# OD12_LCD__Layout.net
KiCad netlist of a schematic drawn in Altium Designer
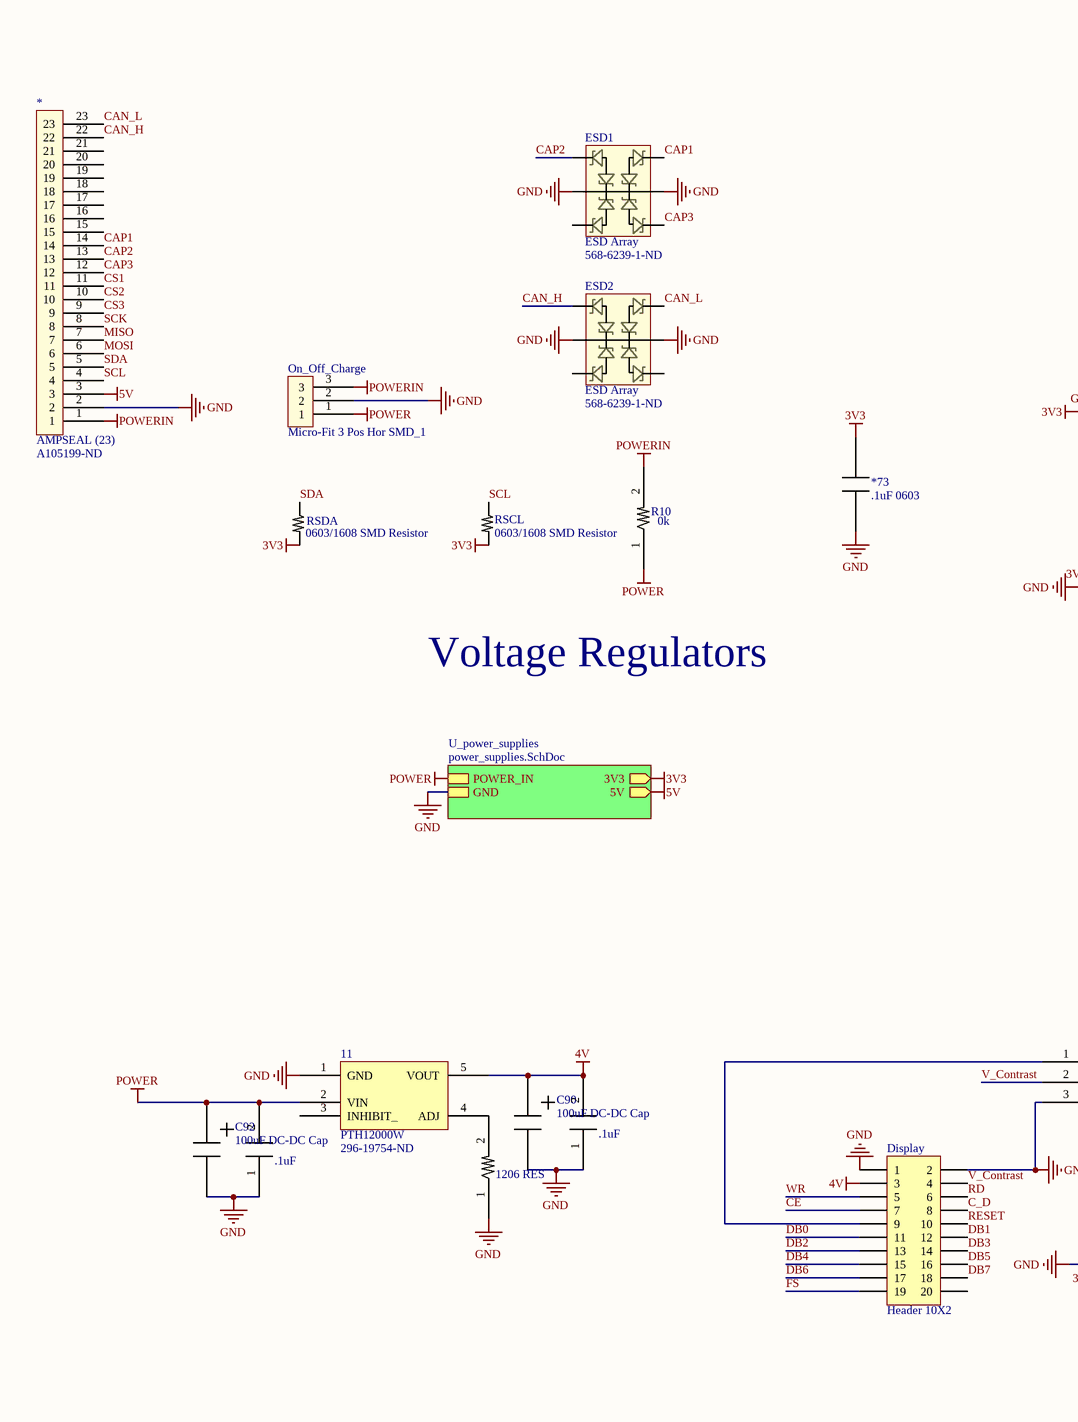
[diagram p0: OD12_LCD__Layout.SchDoc, left]
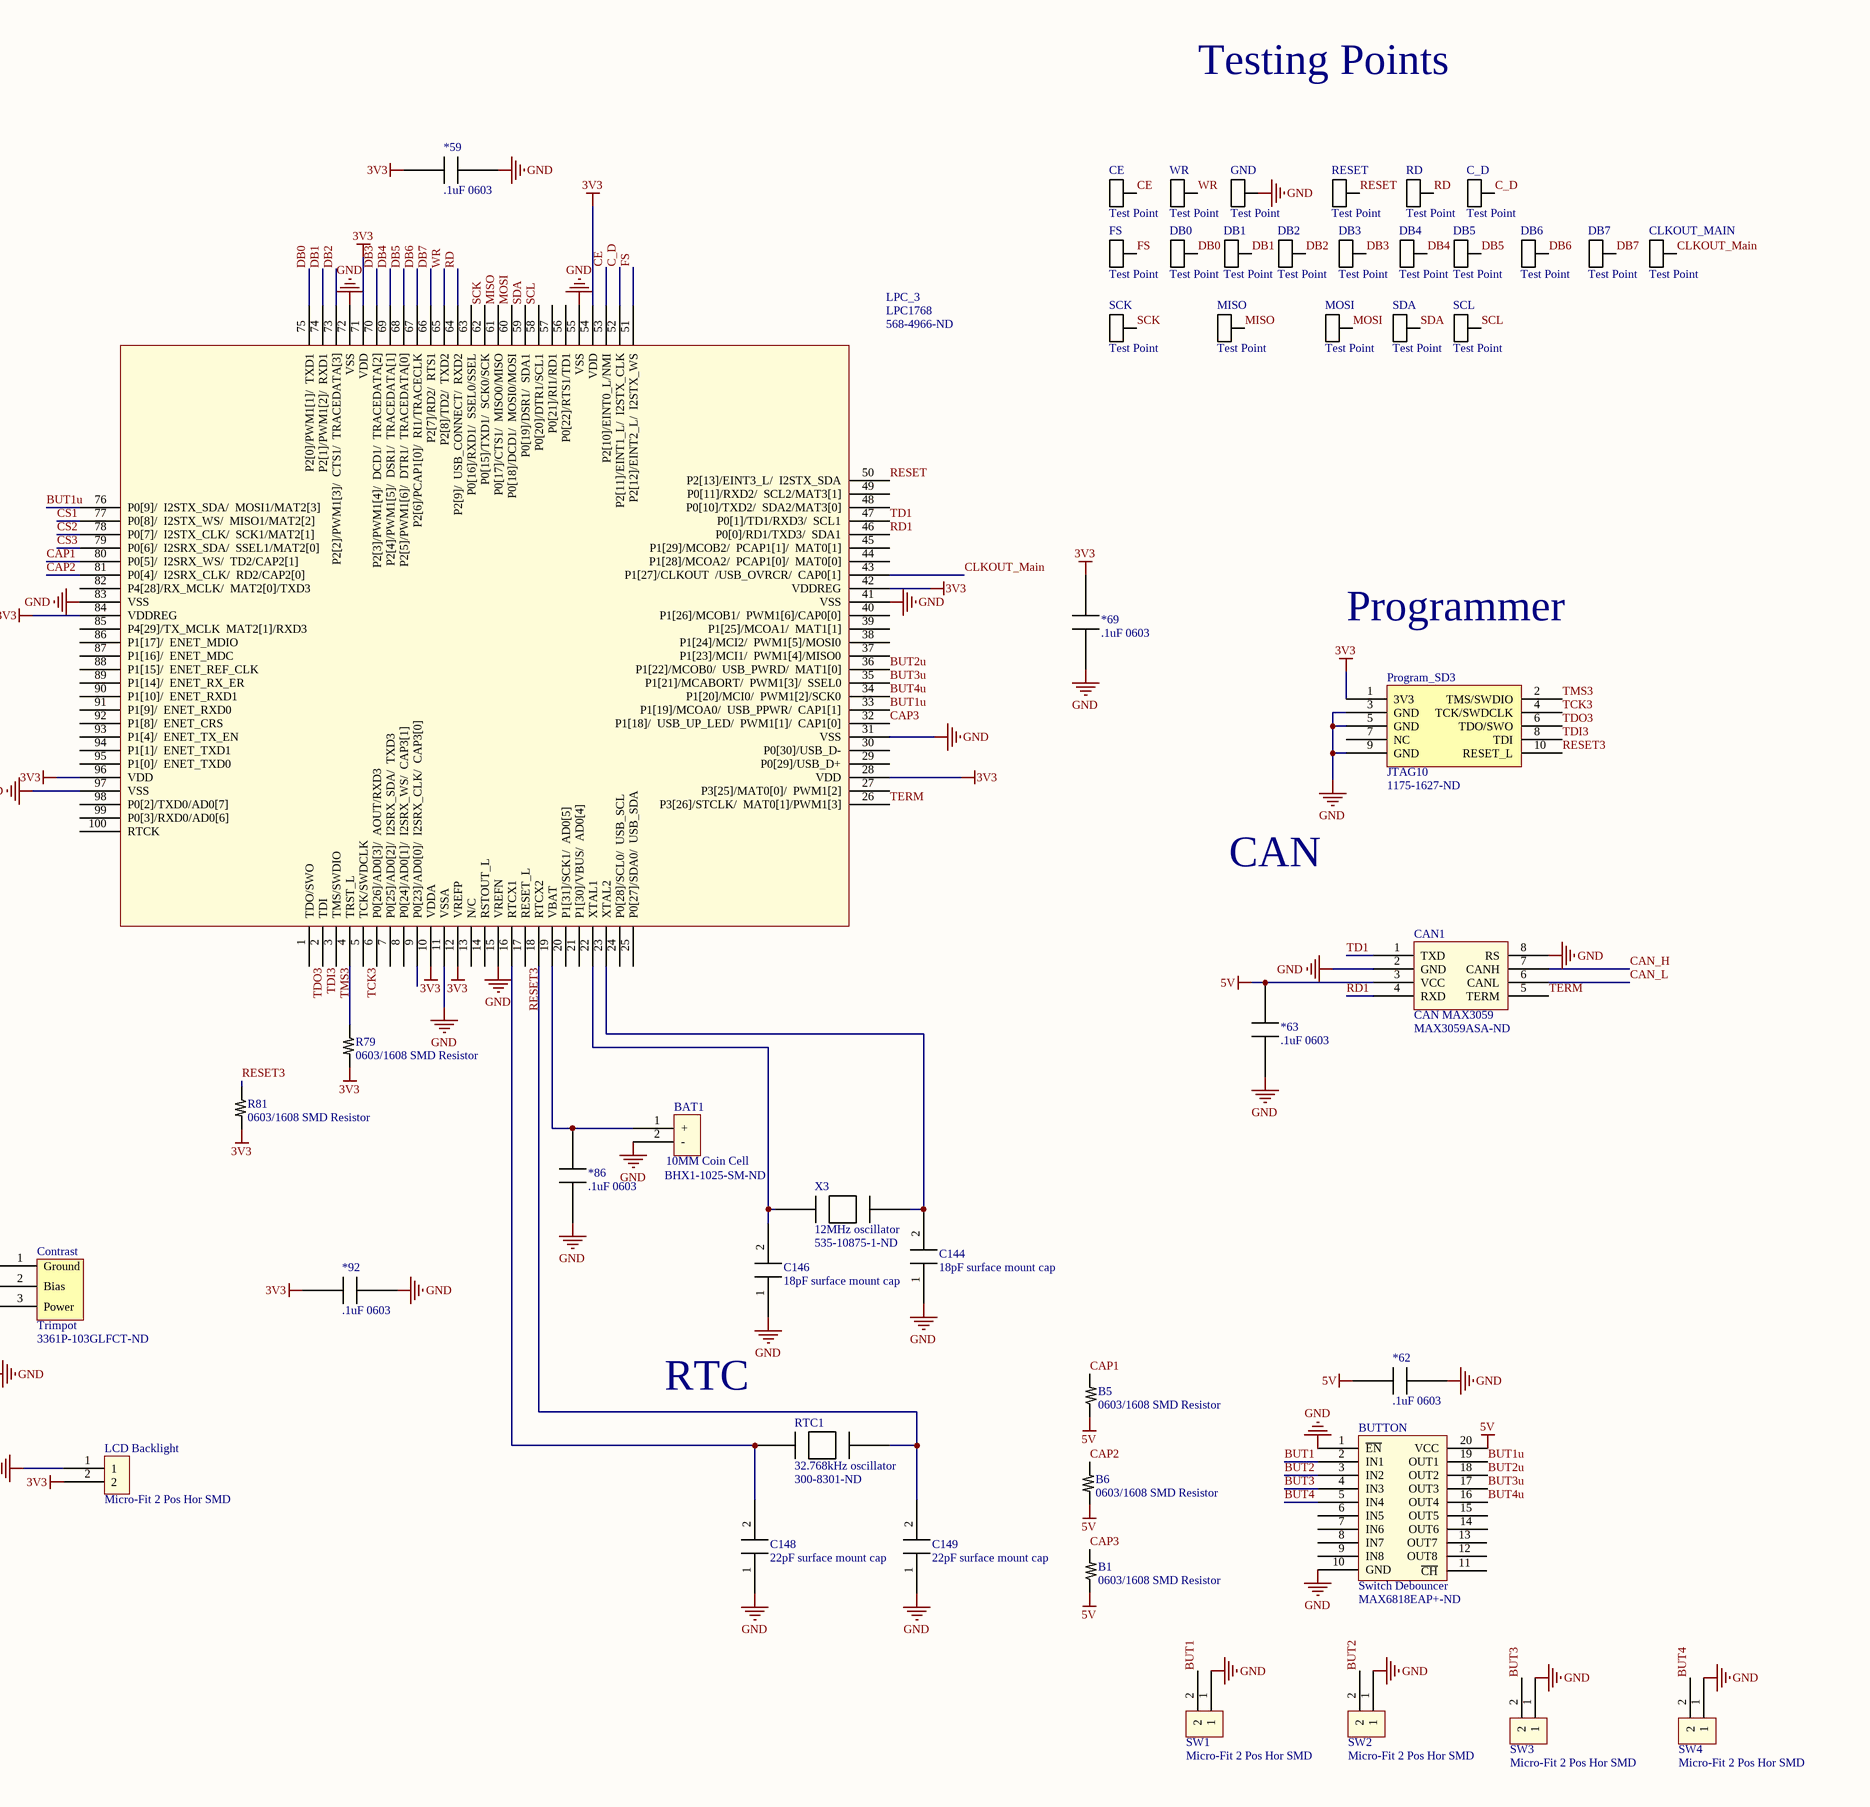
[diagram p1: OD12_LCD__Layout.SchDoc, right]

(export (version "E")
  (design (tool "Eeschema 10.0.6"))
  (components
    (comp (ref "*")
      (value "AMPSEAL (23)")
      (footprint "AMPSEAL (23) HOR")
      (fields (field (name "SUPPLIER PART NUMBER 1") "A105199-ND"))
      (libsource (lib "CornellBajaLibrary") (part "AMPSEAL (23)"))
    )
    (comp (ref "*59")
      (value ".1uF 0603")
      (footprint "0603/1608 SMD Resistor")
      (libsource (lib "CornellBajaLibrary") (part "0603 Cap"))
    )
    (comp (ref "*62")
      (value ".1uF 0603")
      (footprint "0603/1608 SMD Resistor")
      (libsource (lib "CornellBajaLibrary") (part "0603 Cap"))
    )
    (comp (ref "*63")
      (value ".1uF 0603")
      (footprint "0603/1608 SMD Resistor")
      (libsource (lib "CornellBajaLibrary") (part "0603 Cap"))
    )
    (comp (ref "*69")
      (value ".1uF 0603")
      (footprint "0603/1608 SMD Resistor")
      (libsource (lib "CornellBajaLibrary") (part "0603 Cap"))
    )
    (comp (ref "*73")
      (value ".1uF 0603")
      (footprint "0603/1608 SMD Resistor")
      (libsource (lib "CornellBajaLibrary") (part "0603 Cap"))
    )
    (comp (ref "*86")
      (value ".1uF 0603")
      (footprint "0603/1608 SMD Resistor")
      (libsource (lib "CornellBajaLibrary") (part "0603 Cap"))
    )
    (comp (ref "*92")
      (value ".1uF 0603")
      (footprint "0603/1608 SMD Resistor")
      (libsource (lib "CornellBajaLibrary") (part "0603 Cap"))
    )
    (comp (ref "11")
      (value "PTH12000W")
      (footprint "PowerModule")
      (description "Adj 6A 12Vin Power Module")
      (fields (field (name "SUPPLIER PART NUMBER 1") "296-19754-ND"))
      (libsource (lib "CornellBajaLibrary") (part "PTH12000W"))
    )
    (comp (ref "B1")
      (value "0603/1608 SMD Resistor")
      (footprint "0603/1608 SMD Resistor")
      (libsource (lib "CornellBaja") (part "0603/1608 SMD Resistor"))
    )
    (comp (ref "B5")
      (value "0603/1608 SMD Resistor")
      (footprint "0603/1608 SMD Resistor")
      (libsource (lib "CornellBaja") (part "0603/1608 SMD Resistor"))
    )
    (comp (ref "B6")
      (value "0603/1608 SMD Resistor")
      (footprint "0603/1608 SMD Resistor")
      (libsource (lib "CornellBaja") (part "0603/1608 SMD Resistor"))
    )
    (comp (ref "BAT1")
      (value "10MM Coin Cell")
      (footprint "10MM Coin Cell")
      (fields (field (name "SUPPLIER PART NUMBER 1") "BHX1-1025-SM-ND"))
      (libsource (lib "CornellBajaLibrary") (part "10MM Coin Cell"))
    )
    (comp (ref "BUTTON")
      (value "Switch Debouncer")
      (footprint "SOP65P780X199-20N")
      (fields (field (name "SUPPLIER PART NUMBER 1") "MAX6818EAP+-ND"))
      (libsource (lib "CornellBajaLibrary") (part "Switch Debouncer"))
    )
    (comp (ref "C90")
      (value "100uF DC-DC Cap")
      (footprint "100uF DC-DC Cap")
      (libsource (lib "CornellBajaLibrary") (part "100uF DC-DC Cap"))
    )
    (comp (ref "C91")
      (value ".1uF")
      (footprint "1206")
      (description ".1 uF decoupling caps.  you probably want this for your project")
      (libsource (lib "CornellBajaLibrary") (part "1206 CAP"))
    )
    (comp (ref "C92")
      (value "100uF DC-DC Cap")
      (footprint "100uF DC-DC Cap")
      (libsource (lib "CornellBajaLibrary") (part "100uF DC-DC Cap"))
    )
    (comp (ref "C93")
      (value ".1uF")
      (footprint "1206")
      (description ".1 uF decoupling caps.  you probably want this for your project")
      (libsource (lib "CornellBajaLibrary") (part "1206 CAP"))
    )
    (comp (ref "C144")
      (value "18pF surface mount cap")
      (footprint "1206")
      (description "1206 cap for loading a crystal oscillator")
      (libsource (lib "capacitors") (part "18pF surface mount cap"))
    )
    (comp (ref "C146")
      (value "18pF surface mount cap")
      (footprint "1206")
      (description "1206 cap for loading a crystal oscillator")
      (libsource (lib "capacitors") (part "18pF surface mount cap"))
    )
    (comp (ref "C148")
      (value "22pF surface mount cap")
      (footprint "1206")
      (description "1206 cap for loading the crystal oscillator")
      (libsource (lib "Integrated_Library") (part "20pF surface mount cap"))
    )
    (comp (ref "C149")
      (value "22pF surface mount cap")
      (footprint "1206")
      (description "1206 cap for loading the crystal oscillator")
      (libsource (lib "Integrated_Library") (part "20pF surface mount cap"))
    )
    (comp (ref "CAN1")
      (value "CAN MAX3059")
      (footprint "TJA1040")
      (fields (field (name "SUPPLIER PART NUMBER 1") "MAX3059ASA-ND"))
      (libsource (lib "CornellBajaLibrary") (part "CAN MAX3059"))
    )
    (comp (ref "CE")
      (value "Test Point")
      (footprint "Test Point")
      (libsource (lib "CornellBajaLibrary") (part "Test Point"))
    )
    (comp (ref "CLKOUT_MAIN")
      (value "Test Point")
      (footprint "Test Point")
      (libsource (lib "CornellBajaLibrary") (part "Test Point"))
    )
    (comp (ref "Contrast")
      (value "Trimpot")
      (footprint "TrimPot")
      (fields (field (name "SUPPLIER PART NUMBER 1") "3361P-103GLFCT-ND"))
      (libsource (lib "CornellBajaLibrary") (part "Trimpot"))
    )
    (comp (ref "C_D")
      (value "Test Point")
      (footprint "Test Point")
      (libsource (lib "CornellBajaLibrary") (part "Test Point"))
    )
    (comp (ref "DB0")
      (value "Test Point")
      (footprint "Test Point")
      (libsource (lib "CornellBajaLibrary") (part "Test Point"))
    )
    (comp (ref "DB1")
      (value "Test Point")
      (footprint "Test Point")
      (libsource (lib "CornellBajaLibrary") (part "Test Point"))
    )
    (comp (ref "DB2")
      (value "Test Point")
      (footprint "Test Point")
      (libsource (lib "CornellBajaLibrary") (part "Test Point"))
    )
    (comp (ref "DB3")
      (value "Test Point")
      (footprint "Test Point")
      (libsource (lib "CornellBajaLibrary") (part "Test Point"))
    )
    (comp (ref "DB4")
      (value "Test Point")
      (footprint "Test Point")
      (libsource (lib "CornellBajaLibrary") (part "Test Point"))
    )
    (comp (ref "DB5")
      (value "Test Point")
      (footprint "Test Point")
      (libsource (lib "CornellBajaLibrary") (part "Test Point"))
    )
    (comp (ref "DB6")
      (value "Test Point")
      (footprint "Test Point")
      (libsource (lib "CornellBajaLibrary") (part "Test Point"))
    )
    (comp (ref "DB7")
      (value "Test Point")
      (footprint "Test Point")
      (libsource (lib "CornellBajaLibrary") (part "Test Point"))
    )
    (comp (ref "Display")
      (value "Header 10X2")
      (footprint "HDR2X10")
      (description "Header, 10-Pin, Dual row")
      (fields (field (name "PUBLISHER") "Altium Limited"))
      (libsource (lib "Miscellaneous Connectors") (part "Header 10X2"))
    )
    (comp (ref "ESD1")
      (value "ESD Array")
      (footprint "ESD_Array_BZA408B")
      (description "BZA408B,115")
      (fields (field (name "SUPPLIER PART NUMBER 1") "568-6239-1-ND"))
      (libsource (lib "CornellBajaLibrary") (part "ESD Array"))
    )
    (comp (ref "ESD2")
      (value "ESD Array")
      (footprint "ESD_Array_BZA408B")
      (description "BZA408B,115")
      (fields (field (name "SUPPLIER PART NUMBER 1") "568-6239-1-ND"))
      (libsource (lib "CornellBajaLibrary") (part "ESD Array"))
    )
    (comp (ref "FS")
      (value "Test Point")
      (footprint "Test Point")
      (libsource (lib "CornellBajaLibrary") (part "Test Point"))
    )
    (comp (ref "GND")
      (value "Test Point")
      (footprint "Test Point")
      (libsource (lib "CornellBajaLibrary") (part "Test Point"))
    )
    (comp (ref "LCD Backlight")
      (value "Micro-Fit 2 Pos Hor SMD")
      (footprint "Micro-fit 2 Pos Hor SMD - duplicate")
      (libsource (lib "CornellBajaLibrary") (part "Micro-Fit 2 Pos Hor SMD"))
    )
    (comp (ref "LPC_3")
      (value "LPC1768")
      (footprint "LPC1768")
      (description "100 pin ARM microcontroller")
      (fields (field (name "SUPPLIER PART NUMBER 1") "568-4966-ND"))
      (libsource (lib "CornellBajaLibrary") (part "LPC1768"))
    )
    (comp (ref "MISO")
      (value "Test Point")
      (footprint "Test Point")
      (libsource (lib "CornellBajaLibrary") (part "Test Point"))
    )
    (comp (ref "MOSI")
      (value "Test Point")
      (footprint "Test Point")
      (libsource (lib "CornellBajaLibrary") (part "Test Point"))
    )
    (comp (ref "On_Off_Charge")
      (value "Micro-Fit 3 Pos Hor SMD_1")
      (footprint "Micro-fit 3 Pos Hor SMD - duplicate1")
      (libsource (lib "CornellBajaLibrary") (part "Micro-Fit 3 Pos Hor SMD_1"))
    )
    (comp (ref "Program_SD3")
      (value "JTAG10")
      (footprint "JTAG10 Polarity")
      (description "3220-10-0100-00")
      (fields (field (name "SUPPLIER PART NUMBER 1") "1175-1627-ND"))
      (libsource (lib "CornellBajaLibrary") (part "JTAG10"))
    )
    (comp (ref "R10")
      (value "0k")
      (footprint "1206 surface mount resistor")
      (description "Blank surface mount resistor.")
      (libsource (lib "resistors") (part "Blank Resistor Surface mount 1206"))
    )
    (comp (ref "R47")
      (value "1206 RES")
      (footprint "1206")
      (description "0 ohm surface mount resistor.")
      (libsource (lib "CornellBajaLibrary") (part "1206 RES"))
    )
    (comp (ref "R79")
      (value "0603/1608 SMD Resistor")
      (footprint "0603/1608 SMD Resistor")
      (libsource (lib "CornellBajaLibrary") (part "0603/1608 SMD Resistor"))
    )
    (comp (ref "R81")
      (value "0603/1608 SMD Resistor")
      (footprint "0603/1608 SMD Resistor")
      (libsource (lib "CornellBajaLibrary") (part "0603/1608 SMD Resistor"))
    )
    (comp (ref "RD")
      (value "Test Point")
      (footprint "Test Point")
      (libsource (lib "CornellBajaLibrary") (part "Test Point"))
    )
    (comp (ref "RESET")
      (value "Test Point")
      (footprint "Test Point")
      (libsource (lib "CornellBajaLibrary") (part "Test Point"))
    )
    (comp (ref "RSCL")
      (value "0603/1608 SMD Resistor")
      (footprint "0603/1608 SMD Resistor")
      (libsource (lib "CornellBajaLibrary") (part "0603/1608 SMD Resistor"))
    )
    (comp (ref "RSDA")
      (value "0603/1608 SMD Resistor")
      (footprint "0603/1608 SMD Resistor")
      (libsource (lib "CornellBajaLibrary") (part "0603/1608 SMD Resistor"))
    )
    (comp (ref "RTC1")
      (value "32.768kHz oscillator")
      (footprint "32.768kHz Oscillator")
      (description "32.768kHz surface mount oscillator")
      (fields (field (name "SUPPLIER PART NUMBER 1") "300-8301-ND"))
      (libsource (lib "CornellBajaLibrary") (part "32.768kHz"))
    )
    (comp (ref "SCK")
      (value "Test Point")
      (footprint "Test Point")
      (libsource (lib "CornellBajaLibrary") (part "Test Point"))
    )
    (comp (ref "SCL")
      (value "Test Point")
      (footprint "Test Point")
      (libsource (lib "CornellBajaLibrary") (part "Test Point"))
    )
    (comp (ref "SDA")
      (value "Test Point")
      (footprint "Test Point")
      (libsource (lib "CornellBajaLibrary") (part "Test Point"))
    )
    (comp (ref "SW1")
      (value "Micro-Fit 2 Pos Hor SMD")
      (footprint "Micro-fit 2 Pos Hor SMD - duplicate")
      (libsource (lib "") (part "Micro-Fit 2 Pos Hor SMD_1"))
    )
    (comp (ref "SW2")
      (value "Micro-Fit 2 Pos Hor SMD")
      (footprint "Micro-fit 2 Pos Hor SMD - duplicate")
      (libsource (lib "") (part "Micro-Fit 2 Pos Hor SMD_1"))
    )
    (comp (ref "SW3")
      (value "Micro-Fit 2 Pos Hor SMD")
      (footprint "Micro-fit 2 Pos Hor SMD - duplicate")
      (libsource (lib "") (part "Micro-Fit 2 Pos Hor SMD_1"))
    )
    (comp (ref "SW4")
      (value "Micro-Fit 2 Pos Hor SMD")
      (footprint "Micro-fit 2 Pos Hor SMD - duplicate")
      (libsource (lib "") (part "Micro-Fit 2 Pos Hor SMD_1"))
    )
    (comp (ref "WR")
      (value "Test Point")
      (footprint "Test Point")
      (libsource (lib "CornellBajaLibrary") (part "Test Point"))
    )
    (comp (ref "X3")
      (value "12MHz oscillator")
      (footprint "12MHZ Oscillator")
      (description "12MHz surface mount oscillator")
      (fields (field (name "SUPPLIER PART NUMBER 1") "535-10875-1-ND"))
      (libsource (lib "CornellBajaLibrary") (part "12MHz oscillator"))
    )
  )
  (nets
    (net (code "2") (name "/BUT1") (class "Default")
      (node (ref "BUTTON") (pin "2") (pinfunction "IN1_2") (pintype "passive"))
      (node (ref "SW1") (pin "2") (pinfunction "2_2") (pintype "passive"))
    )
    (net (code "3") (name "/BUT1u") (class "Default")
      (node (ref "BUTTON") (pin "19") (pinfunction "OUT1_19") (pintype "passive"))
      (node (ref "LPC_3") (pin "33") (pinfunction "P1[19]/MCOA0/__USB_PPWR/__CAP1[1]_33") (pintype "passive"))
      (node (ref "LPC_3") (pin "76") (pinfunction "P0[9]/__I2STX_SDA/__MOSI1/MAT2[3]_76") (pintype "passive"))
    )
    (net (code "4") (name "/BUT2") (class "Default")
      (node (ref "BUTTON") (pin "3") (pinfunction "IN2_3") (pintype "passive"))
      (node (ref "SW2") (pin "2") (pinfunction "2_2") (pintype "passive"))
    )
    (net (code "5") (name "/BUT2u") (class "Default")
      (node (ref "BUTTON") (pin "18") (pinfunction "OUT2_18") (pintype "passive"))
      (node (ref "LPC_3") (pin "36") (pinfunction "P1[22]/MCOB0/__USB_PWRD/__MAT1[0]_36") (pintype "passive"))
    )
    (net (code "6") (name "/BUT3") (class "Default")
      (node (ref "BUTTON") (pin "4") (pinfunction "IN3_4") (pintype "passive"))
      (node (ref "SW3") (pin "2") (pinfunction "2_2") (pintype "passive"))
    )
    (net (code "7") (name "/BUT3u") (class "Default")
      (node (ref "BUTTON") (pin "17") (pinfunction "OUT3_17") (pintype "passive"))
      (node (ref "LPC_3") (pin "35") (pinfunction "P1[21]/MCABORT/__PWM1[3]/__SSEL0_35") (pintype "passive"))
    )
    (net (code "8") (name "/BUT4") (class "Default")
      (node (ref "BUTTON") (pin "5") (pinfunction "IN4_5") (pintype "passive"))
      (node (ref "SW4") (pin "2") (pinfunction "2_2") (pintype "passive"))
    )
    (net (code "9") (name "/BUT4u") (class "Default")
      (node (ref "BUTTON") (pin "16") (pinfunction "OUT4_16") (pintype "passive"))
      (node (ref "LPC_3") (pin "34") (pinfunction "P1[20]/MCI0/__PWM1[2]/SCK0_34") (pintype "passive"))
    )
    (net (code "10") (name "/CAN_H") (class "Default")
      (node (ref "*") (pin "22") (pinfunction "22_22") (pintype "passive"))
      (node (ref "CAN1") (pin "7") (pinfunction "CANH_7") (pintype "passive"))
      (node (ref "ESD2") (pin "1") (pinfunction "1_1") (pintype "passive"))
    )
    (net (code "11") (name "/CAN_L") (class "Default")
      (node (ref "*") (pin "23") (pinfunction "23_23") (pintype "passive"))
      (node (ref "CAN1") (pin "6") (pinfunction "CANL_6") (pintype "passive"))
      (node (ref "ESD2") (pin "6") (pinfunction "6_6") (pintype "passive"))
    )
    (net (code "12") (name "/CAP1") (class "Default")
      (node (ref "*") (pin "14") (pinfunction "14_14") (pintype "passive"))
      (node (ref "B5") (pin "1") (pinfunction "1_1") (pintype "passive"))
      (node (ref "ESD1") (pin "6") (pinfunction "6_6") (pintype "passive"))
      (node (ref "LPC_3") (pin "80") (pinfunction "P0[5]/__I2SRX_WS/__TD2/CAP2[1]_80") (pintype "passive"))
    )
    (net (code "13") (name "/CAP2") (class "Default")
      (node (ref "*") (pin "13") (pinfunction "13_13") (pintype "passive"))
      (node (ref "B6") (pin "2") (pinfunction "2_2") (pintype "passive"))
      (node (ref "ESD1") (pin "1") (pinfunction "1_1") (pintype "passive"))
      (node (ref "LPC_3") (pin "81") (pinfunction "P0[4]/__I2SRX_CLK/__RD2/CAP2[0]_81") (pintype "passive"))
    )
    (net (code "14") (name "/CAP3") (class "Default")
      (node (ref "*") (pin "12") (pinfunction "12_12") (pintype "passive"))
      (node (ref "B1") (pin "1") (pinfunction "1_1") (pintype "passive"))
      (node (ref "ESD1") (pin "4") (pinfunction "4_4") (pintype "passive"))
      (node (ref "LPC_3") (pin "32") (pinfunction "P1[18]/__USB_UP_LED/__PWM1[1]/__CAP1[0]_32") (pintype "passive"))
    )
    (net (code "15") (name "/CE") (class "Default")
      (node (ref "CE") (pin "1") (pinfunction "1_1") (pintype "passive"))
      (node (ref "Display") (pin "7") (pinfunction "7_7") (pintype "passive"))
      (node (ref "LPC_3") (pin "53") (pinfunction "P2[10]/EINT0_L/NMI_53") (pintype "passive"))
    )
    (net (code "16") (name "/CLKOUT_Main") (class "Default")
      (node (ref "CLKOUT_MAIN") (pin "1") (pinfunction "1_1") (pintype "passive"))
      (node (ref "LPC_3") (pin "43") (pinfunction "P1[27]/CLKOUT__/USB_OVRCR/__CAP0[1]_43") (pintype "passive"))
    )
    (net (code "17") (name "/CS1") (class "Default")
      (node (ref "*") (pin "11") (pinfunction "11_11") (pintype "passive"))
      (node (ref "LPC_3") (pin "77") (pinfunction "P0[8]/__I2STX_WS/__MISO1/MAT2[2]_77") (pintype "passive"))
    )
    (net (code "18") (name "/CS2") (class "Default")
      (node (ref "*") (pin "10") (pinfunction "10_10") (pintype "passive"))
      (node (ref "LPC_3") (pin "78") (pinfunction "P0[7]/__I2STX_CLK/__SCK1/MAT2[1]_78") (pintype "passive"))
    )
    (net (code "19") (name "/CS3") (class "Default")
      (node (ref "*") (pin "9") (pinfunction "9_9") (pintype "passive"))
      (node (ref "LPC_3") (pin "79") (pinfunction "P0[6]/__I2SRX_SDA/__SSEL1/MAT2[0]_79") (pintype "passive"))
    )
    (net (code "20") (name "/C_D") (class "Default")
      (node (ref "C_D") (pin "1") (pinfunction "1_1") (pintype "passive"))
      (node (ref "Display") (pin "8") (pinfunction "8_8") (pintype "passive"))
      (node (ref "LPC_3") (pin "52") (pinfunction "P2[11]/EINT1_L/__I2STX_CLK_52") (pintype "passive"))
    )
    (net (code "21") (name "/DB0") (class "Default")
      (node (ref "DB0") (pin "1") (pinfunction "1_1") (pintype "passive"))
      (node (ref "Display") (pin "11") (pinfunction "11_11") (pintype "passive"))
      (node (ref "LPC_3") (pin "75") (pinfunction "P2[0]/PWM1[1]/__TXD1_75") (pintype "passive"))
    )
    (net (code "22") (name "/DB1") (class "Default")
      (node (ref "DB1") (pin "1") (pinfunction "1_1") (pintype "passive"))
      (node (ref "Display") (pin "12") (pinfunction "12_12") (pintype "passive"))
      (node (ref "LPC_3") (pin "74") (pinfunction "P2[1]/PWM1[2]/__RXD1_74") (pintype "passive"))
    )
    (net (code "23") (name "/DB2") (class "Default")
      (node (ref "DB2") (pin "1") (pinfunction "1_1") (pintype "passive"))
      (node (ref "Display") (pin "13") (pinfunction "13_13") (pintype "passive"))
      (node (ref "LPC_3") (pin "73") (pinfunction "P2[2]/PWM1[3]/__CTS1/__TRACEDATA[3]_73") (pintype "passive"))
    )
    (net (code "24") (name "/DB3") (class "Default")
      (node (ref "DB3") (pin "1") (pinfunction "1_1") (pintype "passive"))
      (node (ref "Display") (pin "14") (pinfunction "14_14") (pintype "passive"))
      (node (ref "LPC_3") (pin "70") (pinfunction "P2[3]/PWM1[4]/__DCD1/__TRACEDATA[2]_70") (pintype "passive"))
    )
    (net (code "25") (name "/DB4") (class "Default")
      (node (ref "DB4") (pin "1") (pinfunction "1_1") (pintype "passive"))
      (node (ref "Display") (pin "15") (pinfunction "15_15") (pintype "passive"))
      (node (ref "LPC_3") (pin "69") (pinfunction "P2[4]/PWM1[5]/__DSR1/__TRACEDATA[1]_69") (pintype "passive"))
    )
    (net (code "26") (name "/DB5") (class "Default")
      (node (ref "DB5") (pin "1") (pinfunction "1_1") (pintype "passive"))
      (node (ref "Display") (pin "16") (pinfunction "16_16") (pintype "passive"))
      (node (ref "LPC_3") (pin "68") (pinfunction "P2[5]/PWM1[6]/__DTR1/__TRACEDATA[0]_68") (pintype "passive"))
    )
    (net (code "27") (name "/DB6") (class "Default")
      (node (ref "DB6") (pin "1") (pinfunction "1_1") (pintype "passive"))
      (node (ref "Display") (pin "17") (pinfunction "17_17") (pintype "passive"))
      (node (ref "LPC_3") (pin "67") (pinfunction "P2[6]/PCAP1[0]/__RI1/TRACECLK_67") (pintype "passive"))
    )
    (net (code "28") (name "/DB7") (class "Default")
      (node (ref "DB7") (pin "1") (pinfunction "1_1") (pintype "passive"))
      (node (ref "Display") (pin "18") (pinfunction "18_18") (pintype "passive"))
      (node (ref "LPC_3") (pin "66") (pinfunction "P2[7]/RD2/__RTS1_66") (pintype "passive"))
    )
    (net (code "29") (name "/FS") (class "Default")
      (node (ref "Display") (pin "19") (pinfunction "19_19") (pintype "passive"))
      (node (ref "FS") (pin "1") (pinfunction "1_1") (pintype "passive"))
      (node (ref "LPC_3") (pin "51") (pinfunction "P2[12]/EINT2_L/__I2STX_WS_51") (pintype "passive"))
    )
    (net (code "30") (name "/MISO") (class "Default")
      (node (ref "*") (pin "7") (pinfunction "7_7") (pintype "passive"))
      (node (ref "LPC_3") (pin "61") (pinfunction "P0[17]/CTS1/__MISO0/MISO_61") (pintype "passive"))
      (node (ref "MISO") (pin "1") (pinfunction "1_1") (pintype "passive"))
    )
    (net (code "31") (name "/MOSI") (class "Default")
      (node (ref "*") (pin "6") (pinfunction "6_6") (pintype "passive"))
      (node (ref "LPC_3") (pin "60") (pinfunction "P0[18]/DCD1/__MOSI0/MOSI_60") (pintype "passive"))
      (node (ref "MOSI") (pin "1") (pinfunction "1_1") (pintype "passive"))
    )
    (net (code "32") (name "/RD") (class "Default")
      (node (ref "Display") (pin "6") (pinfunction "6_6") (pintype "passive"))
      (node (ref "LPC_3") (pin "64") (pinfunction "P2[9]/__USB_CONNECT/__RXD2_64") (pintype "passive"))
      (node (ref "RD") (pin "1") (pinfunction "1_1") (pintype "passive"))
    )
    (net (code "33") (name "/RD1") (class "Default")
      (node (ref "CAN1") (pin "4") (pinfunction "RXD_4") (pintype "passive"))
      (node (ref "LPC_3") (pin "46") (pinfunction "P0[0]/RD1/TXD3/__SDA1_46") (pintype "passive"))
    )
    (net (code "34") (name "/RESET") (class "Default")
      (node (ref "Display") (pin "10") (pinfunction "10_10") (pintype "passive"))
      (node (ref "LPC_3") (pin "50") (pinfunction "P2[13]/EINT3_L/__I2STX_SDA_50") (pintype "passive"))
      (node (ref "RESET") (pin "1") (pinfunction "1_1") (pintype "passive"))
    )
    (net (code "35") (name "/RESET3") (class "Default")
      (node (ref "LPC_3") (pin "17") (pinfunction "RESET_L_17") (pintype "passive"))
      (node (ref "Program_SD3") (pin "10") (pinfunction "RESET_L_10") (pintype "passive"))
      (node (ref "R81") (pin "2") (pinfunction "2_2") (pintype "passive"))
    )
    (net (code "36") (name "/SCK") (class "Default")
      (node (ref "*") (pin "8") (pinfunction "8_8") (pintype "passive"))
      (node (ref "LPC_3") (pin "62") (pinfunction "P0[15]/TXD1/__SCK0/SCK_62") (pintype "passive"))
      (node (ref "SCK") (pin "1") (pinfunction "1_1") (pintype "passive"))
    )
    (net (code "37") (name "/SCL") (class "Default")
      (node (ref "*") (pin "4") (pinfunction "4_4") (pintype "passive"))
      (node (ref "LPC_3") (pin "58") (pinfunction "P0[20]/DTR1/SCL1_58") (pintype "passive"))
      (node (ref "RSCL") (pin "2") (pinfunction "2_2") (pintype "passive"))
      (node (ref "SCL") (pin "1") (pinfunction "1_1") (pintype "passive"))
    )
    (net (code "38") (name "/SDA") (class "Default")
      (node (ref "*") (pin "5") (pinfunction "5_5") (pintype "passive"))
      (node (ref "LPC_3") (pin "59") (pinfunction "P0[19]/DSR1/__SDA1_59") (pintype "passive"))
      (node (ref "RSDA") (pin "2") (pinfunction "2_2") (pintype "passive"))
      (node (ref "SDA") (pin "1") (pinfunction "1_1") (pintype "passive"))
    )
    (net (code "39") (name "/TCK3") (class "Default")
      (node (ref "LPC_3") (pin "5") (pinfunction "TCK/SWDCLK_5") (pintype "passive"))
      (node (ref "Program_SD3") (pin "4") (pinfunction "TCK/SWDCLK_4") (pintype "passive"))
    )
    (net (code "40") (name "/TD1") (class "Default")
      (node (ref "CAN1") (pin "1") (pinfunction "TXD_1") (pintype "passive"))
      (node (ref "LPC_3") (pin "47") (pinfunction "P0[1]/TD1/RXD3/__SCL1_47") (pintype "passive"))
    )
    (net (code "41") (name "/TDI3") (class "Default")
      (node (ref "LPC_3") (pin "2") (pinfunction "TDI_2") (pintype "passive"))
      (node (ref "Program_SD3") (pin "8") (pinfunction "TDI_8") (pintype "passive"))
    )
    (net (code "42") (name "/TDO3") (class "Default")
      (node (ref "LPC_3") (pin "1") (pinfunction "TDO/SWO_1") (pintype "passive"))
      (node (ref "Program_SD3") (pin "6") (pinfunction "TDO/SWO_6") (pintype "passive"))
    )
    (net (code "43") (name "/TERM") (class "Default")
      (node (ref "CAN1") (pin "5") (pinfunction "TERM_5") (pintype "passive"))
      (node (ref "LPC_3") (pin "26") (pinfunction "P3[26]/STCLK/__MAT0[1]/PWM1[3]_26") (pintype "passive"))
    )
    (net (code "44") (name "/TMS3") (class "Default")
      (node (ref "LPC_3") (pin "3") (pinfunction "TMS/SWDIO_3") (pintype "passive"))
      (node (ref "Program_SD3") (pin "2") (pinfunction "TMS/SWDIO_2") (pintype "passive"))
    )
    (net (code "45") (name "/V_Contrast") (class "Default")
      (node (ref "Contrast") (pin "2") (pinfunction "Bias_2") (pintype "passive"))
      (node (ref "Display") (pin "4") (pinfunction "4_4") (pintype "passive"))
    )
    (net (code "46") (name "/WR") (class "Default")
      (node (ref "Display") (pin "5") (pinfunction "5_5") (pintype "passive"))
      (node (ref "LPC_3") (pin "65") (pinfunction "P2[8]/TD2/__TXD2_65") (pintype "passive"))
      (node (ref "WR") (pin "1") (pinfunction "1_1") (pintype "passive"))
    )
    (net (code "47") (name "3V3") (class "Default")
      (node (ref "*59") (pin "2") (pinfunction "2_2") (pintype "passive"))
      (node (ref "*69") (pin "1") (pinfunction "1_1") (pintype "passive"))
      (node (ref "*73") (pin "2") (pinfunction "2_2") (pintype "passive"))
      (node (ref "*92") (pin "2") (pinfunction "2_2") (pintype "passive"))
      (node (ref "LCD Backlight") (pin "2") (pinfunction "2_2") (pintype "passive"))
      (node (ref "LPC_3") (pin "10") (pinfunction "VDDA_10") (pintype "passive"))
      (node (ref "LPC_3") (pin "12") (pinfunction "VREFP_12") (pintype "passive"))
      (node (ref "LPC_3") (pin "28") (pinfunction "VDD_28") (pintype "passive"))
      (node (ref "LPC_3") (pin "42") (pinfunction "VDDREG_42") (pintype "passive"))
      (node (ref "LPC_3") (pin "54") (pinfunction "VDD_54") (pintype "passive"))
      (node (ref "LPC_3") (pin "71") (pinfunction "VDD_71") (pintype "passive"))
      (node (ref "LPC_3") (pin "84") (pinfunction "VDDREG_84") (pintype "passive"))
      (node (ref "LPC_3") (pin "96") (pinfunction "VDD_96") (pintype "passive"))
      (node (ref "Program_SD3") (pin "1") (pinfunction "3V3_1") (pintype "passive"))
      (node (ref "R79") (pin "1") (pinfunction "1_1") (pintype "passive"))
      (node (ref "R81") (pin "1") (pinfunction "1_1") (pintype "passive"))
      (node (ref "RSCL") (pin "1") (pinfunction "1_1") (pintype "passive"))
      (node (ref "RSDA") (pin "1") (pinfunction "1_1") (pintype "passive"))
    )
    (net (code "48") (name "4V") (class "Default")
      (node (ref "11") (pin "5") (pinfunction "VOUT_5") (pintype "passive"))
      (node (ref "C90") (pin "1") (pinfunction "+_1") (pintype "passive"))
      (node (ref "C91") (pin "2") (pinfunction "2_2") (pintype "passive"))
      (node (ref "Display") (pin "3") (pinfunction "3_3") (pintype "passive"))
    )
    (net (code "49") (name "5V") (class "Default")
      (node (ref "*") (pin "3") (pinfunction "3_3") (pintype "passive"))
      (node (ref "*62") (pin "2") (pinfunction "2_2") (pintype "passive"))
      (node (ref "*63") (pin "2") (pinfunction "2_2") (pintype "passive"))
      (node (ref "B1") (pin "2") (pinfunction "2_2") (pintype "passive"))
      (node (ref "B5") (pin "2") (pinfunction "2_2") (pintype "passive"))
      (node (ref "B6") (pin "1") (pinfunction "1_1") (pintype "passive"))
      (node (ref "BUTTON") (pin "20") (pinfunction "VCC_20") (pintype "passive"))
      (node (ref "CAN1") (pin "3") (pinfunction "VCC_3") (pintype "passive"))
    )
    (net (code "50") (name "GND") (class "Default")
      (node (ref "*") (pin "2") (pinfunction "2_2") (pintype "passive"))
      (node (ref "*59") (pin "1") (pinfunction "1_1") (pintype "passive"))
      (node (ref "*62") (pin "1") (pinfunction "1_1") (pintype "passive"))
      (node (ref "*63") (pin "1") (pinfunction "1_1") (pintype "passive"))
      (node (ref "*69") (pin "2") (pinfunction "2_2") (pintype "passive"))
      (node (ref "*73") (pin "1") (pinfunction "1_1") (pintype "passive"))
      (node (ref "*86") (pin "2") (pinfunction "2_2") (pintype "passive"))
      (node (ref "*92") (pin "1") (pinfunction "1_1") (pintype "passive"))
      (node (ref "11") (pin "1") (pinfunction "GND_1") (pintype "passive"))
      (node (ref "BAT1") (pin "2") (pinfunction "-_2") (pintype "passive"))
      (node (ref "BUTTON") (pin "1") (pinfunction "~{EN}_1") (pintype "passive"))
      (node (ref "BUTTON") (pin "10") (pinfunction "GND_10") (pintype "passive"))
      (node (ref "C144") (pin "1") (pinfunction "1_1") (pintype "passive"))
      (node (ref "C146") (pin "1") (pinfunction "1_1") (pintype "passive"))
      (node (ref "C148") (pin "1") (pinfunction "1_1") (pintype "passive"))
      (node (ref "C149") (pin "1") (pinfunction "1_1") (pintype "passive"))
      (node (ref "C90") (pin "2") (pinfunction "-_2") (pintype "passive"))
      (node (ref "C91") (pin "1") (pinfunction "1_1") (pintype "passive"))
      (node (ref "C92") (pin "2") (pinfunction "-_2") (pintype "passive"))
      (node (ref "C93") (pin "1") (pinfunction "1_1") (pintype "passive"))
      (node (ref "CAN1") (pin "2") (pinfunction "GND_2") (pintype "passive"))
      (node (ref "CAN1") (pin "8") (pinfunction "RS_8") (pintype "passive"))
      (node (ref "Contrast") (pin "3") (pinfunction "Power_3") (pintype "passive"))
      (node (ref "Display") (pin "1") (pinfunction "1_1") (pintype "passive"))
      (node (ref "Display") (pin "2") (pinfunction "2_2") (pintype "passive"))
      (node (ref "ESD1") (pin "2") (pinfunction "2_2") (pintype "passive"))
      (node (ref "ESD1") (pin "5") (pinfunction "5_5") (pintype "passive"))
      (node (ref "ESD2") (pin "2") (pinfunction "2_2") (pintype "passive"))
      (node (ref "ESD2") (pin "5") (pinfunction "5_5") (pintype "passive"))
      (node (ref "GND") (pin "1") (pinfunction "1_1") (pintype "passive"))
      (node (ref "LCD Backlight") (pin "1") (pinfunction "1_1") (pintype "passive"))
      (node (ref "LPC_3") (pin "11") (pinfunction "VSSA_11") (pintype "passive"))
      (node (ref "LPC_3") (pin "15") (pinfunction "VREFN_15") (pintype "passive"))
      (node (ref "LPC_3") (pin "31") (pinfunction "VSS_31") (pintype "passive"))
      (node (ref "LPC_3") (pin "41") (pinfunction "VSS_41") (pintype "passive"))
      (node (ref "LPC_3") (pin "55") (pinfunction "VSS_55") (pintype "passive"))
      (node (ref "LPC_3") (pin "72") (pinfunction "VSS_72") (pintype "passive"))
      (node (ref "LPC_3") (pin "83") (pinfunction "VSS_83") (pintype "passive"))
      (node (ref "LPC_3") (pin "97") (pinfunction "VSS_97") (pintype "passive"))
      (node (ref "On_Off_Charge") (pin "2") (pinfunction "2_2") (pintype "passive"))
      (node (ref "Program_SD3") (pin "3") (pinfunction "GND_3") (pintype "passive"))
      (node (ref "Program_SD3") (pin "5") (pinfunction "GND_5") (pintype "passive"))
      (node (ref "Program_SD3") (pin "9") (pinfunction "GND_9") (pintype "passive"))
      (node (ref "R47") (pin "1") (pinfunction "1_1") (pintype "passive"))
      (node (ref "SW1") (pin "1") (pinfunction "1_1") (pintype "passive"))
      (node (ref "SW2") (pin "1") (pinfunction "1_1") (pintype "passive"))
      (node (ref "SW3") (pin "1") (pinfunction "1_1") (pintype "passive"))
      (node (ref "SW4") (pin "1") (pinfunction "1_1") (pintype "passive"))
    )
    (net (code "51") (name "Net-(11-ADJ)") (class "Default")
      (node (ref "11") (pin "4") (pinfunction "ADJ_4") (pintype "passive"))
      (node (ref "R47") (pin "2") (pinfunction "2_2") (pintype "passive"))
    )
    (net (code "52") (name "Net-(BAT1-+)") (class "Default")
      (node (ref "*86") (pin "1") (pinfunction "1_1") (pintype "passive"))
      (node (ref "BAT1") (pin "1") (pinfunction "+_1") (pintype "passive"))
      (node (ref "LPC_3") (pin "19") (pinfunction "VBAT_19") (pintype "passive"))
    )
    (net (code "53") (name "Net-(Contrast-Ground)") (class "Default")
      (node (ref "Contrast") (pin "1") (pinfunction "Ground_1") (pintype "passive"))
      (node (ref "Display") (pin "9") (pinfunction "9_9") (pintype "passive"))
    )
    (net (code "54") (name "Net-(LPC_3-RTCX1)") (class "Default")
      (node (ref "C148") (pin "2") (pinfunction "2_2") (pintype "passive"))
      (node (ref "LPC_3") (pin "16") (pinfunction "RTCX1_16") (pintype "passive"))
      (node (ref "RTC1") (pin "1") (pinfunction "1_1") (pintype "passive"))
    )
    (net (code "55") (name "Net-(LPC_3-RTCX2)") (class "Default")
      (node (ref "C149") (pin "2") (pinfunction "2_2") (pintype "passive"))
      (node (ref "LPC_3") (pin "18") (pinfunction "RTCX2_18") (pintype "passive"))
      (node (ref "RTC1") (pin "2") (pinfunction "2_2") (pintype "passive"))
    )
    (net (code "56") (name "Net-(LPC_3-TRST_L)") (class "Default")
      (node (ref "LPC_3") (pin "4") (pinfunction "TRST_L_4") (pintype "passive"))
      (node (ref "R79") (pin "2") (pinfunction "2_2") (pintype "passive"))
    )
    (net (code "57") (name "Net-(LPC_3-XTAL1)") (class "Default")
      (node (ref "C146") (pin "2") (pinfunction "2_2") (pintype "passive"))
      (node (ref "LPC_3") (pin "22") (pinfunction "XTAL1_22") (pintype "passive"))
      (node (ref "X3") (pin "2") (pinfunction "2_2") (pintype "passive"))
    )
    (net (code "58") (name "Net-(LPC_3-XTAL2)") (class "Default")
      (node (ref "C144") (pin "2") (pinfunction "2_2") (pintype "passive"))
      (node (ref "LPC_3") (pin "23") (pinfunction "XTAL2_23") (pintype "passive"))
      (node (ref "X3") (pin "1") (pinfunction "1_1") (pintype "passive"))
    )
    (net (code "59") (name "POWER") (class "Default")
      (node (ref "11") (pin "2") (pinfunction "VIN_2") (pintype "passive"))
      (node (ref "C92") (pin "1") (pinfunction "+_1") (pintype "passive"))
      (node (ref "C93") (pin "2") (pinfunction "2_2") (pintype "passive"))
      (node (ref "On_Off_Charge") (pin "1") (pinfunction "1_1") (pintype "passive"))
      (node (ref "R10") (pin "1") (pinfunction "1_1") (pintype "passive"))
    )
    (net (code "60") (name "POWERIN") (class "Default")
      (node (ref "*") (pin "1") (pinfunction "1_1") (pintype "passive"))
      (node (ref "On_Off_Charge") (pin "3") (pinfunction "3_3") (pintype "passive"))
      (node (ref "R10") (pin "2") (pinfunction "2_2") (pintype "passive"))
    )
    (net (code "61") (name "unconnected-(*-Pad15)") (class "Default")
      (node (ref "*") (pin "15") (pinfunction "15_15") (pintype "passive"))
    )
    (net (code "62") (name "unconnected-(*-Pad16)") (class "Default")
      (node (ref "*") (pin "16") (pinfunction "16_16") (pintype "passive"))
    )
    (net (code "63") (name "unconnected-(*-Pad17)") (class "Default")
      (node (ref "*") (pin "17") (pinfunction "17_17") (pintype "passive"))
    )
    (net (code "64") (name "unconnected-(*-Pad18)") (class "Default")
      (node (ref "*") (pin "18") (pinfunction "18_18") (pintype "passive"))
    )
    (net (code "65") (name "unconnected-(*-Pad19)") (class "Default")
      (node (ref "*") (pin "19") (pinfunction "19_19") (pintype "passive"))
    )
    (net (code "66") (name "unconnected-(*-Pad20)") (class "Default")
      (node (ref "*") (pin "20") (pinfunction "20_20") (pintype "passive"))
    )
    (net (code "67") (name "unconnected-(*-Pad21)") (class "Default")
      (node (ref "*") (pin "21") (pinfunction "21_21") (pintype "passive"))
    )
    (net (code "68") (name "unconnected-(11-INHIBIT_-Pad3)") (class "Default")
      (node (ref "11") (pin "3") (pinfunction "INHIBIT__3") (pintype "passive"))
    )
    (net (code "69") (name "unconnected-(BUTTON-IN5-Pad6)") (class "Default")
      (node (ref "BUTTON") (pin "6") (pinfunction "IN5_6") (pintype "passive"))
    )
    (net (code "70") (name "unconnected-(BUTTON-IN6-Pad7)") (class "Default")
      (node (ref "BUTTON") (pin "7") (pinfunction "IN6_7") (pintype "passive"))
    )
    (net (code "71") (name "unconnected-(BUTTON-IN7-Pad8)") (class "Default")
      (node (ref "BUTTON") (pin "8") (pinfunction "IN7_8") (pintype "passive"))
    )
    (net (code "72") (name "unconnected-(BUTTON-IN8-Pad9)") (class "Default")
      (node (ref "BUTTON") (pin "9") (pinfunction "IN8_9") (pintype "passive"))
    )
    (net (code "73") (name "unconnected-(BUTTON-OUT5-Pad15)") (class "Default")
      (node (ref "BUTTON") (pin "15") (pinfunction "OUT5_15") (pintype "passive"))
    )
    (net (code "74") (name "unconnected-(BUTTON-OUT6-Pad14)") (class "Default")
      (node (ref "BUTTON") (pin "14") (pinfunction "OUT6_14") (pintype "passive"))
    )
    (net (code "75") (name "unconnected-(BUTTON-OUT7-Pad13)") (class "Default")
      (node (ref "BUTTON") (pin "13") (pinfunction "OUT7_13") (pintype "passive"))
    )
    (net (code "76") (name "unconnected-(BUTTON-OUT8-Pad12)") (class "Default")
      (node (ref "BUTTON") (pin "12") (pinfunction "OUT8_12") (pintype "passive"))
    )
    (net (code "77") (name "unconnected-(BUTTON-~{CH}-Pad11)") (class "Default")
      (node (ref "BUTTON") (pin "11") (pinfunction "~{CH}_11") (pintype "passive"))
    )
    (net (code "78") (name "unconnected-(Display-Pad20)") (class "Default")
      (node (ref "Display") (pin "20") (pinfunction "20_20") (pintype "passive"))
    )
    (net (code "79") (name "unconnected-(ESD1-Pad3)") (class "Default")
      (node (ref "ESD1") (pin "3") (pinfunction "3_3") (pintype "passive"))
    )
    (net (code "80") (name "unconnected-(ESD2-Pad3)") (class "Default")
      (node (ref "ESD2") (pin "3") (pinfunction "3_3") (pintype "passive"))
    )
    (net (code "81") (name "unconnected-(ESD2-Pad4)") (class "Default")
      (node (ref "ESD2") (pin "4") (pinfunction "4_4") (pintype "passive"))
    )
    (net (code "82") (name "unconnected-(LPC_3-N{slash}C-Pad13)") (class "Default")
      (node (ref "LPC_3") (pin "13") (pinfunction "N/C_13") (pintype "passive"))
    )
    (net (code "83") (name "unconnected-(LPC_3-P0[2]{slash}TXD0{slash}AD0[7]-Pad98)") (class "Default")
      (node (ref "LPC_3") (pin "98") (pinfunction "P0[2]/TXD0/AD0[7]_98") (pintype "passive"))
    )
    (net (code "84") (name "unconnected-(LPC_3-P0[3]{slash}RXD0{slash}AD0[6]-Pad99)") (class "Default")
      (node (ref "LPC_3") (pin "99") (pinfunction "P0[3]/RXD0/AD0[6]_99") (pintype "passive"))
    )
    (net (code "85") (name "unconnected-(LPC_3-P0[10]{slash}TXD2{slash}__SDA2{slash}MAT3[0]-Pad48)") (class "Default")
      (node (ref "LPC_3") (pin "48") (pinfunction "P0[10]/TXD2/__SDA2/MAT3[0]_48") (pintype "passive"))
    )
    (net (code "86") (name "unconnected-(LPC_3-P0[11]{slash}RXD2{slash}__SCL2{slash}MAT3[1]-Pad49)") (class "Default")
      (node (ref "LPC_3") (pin "49") (pinfunction "P0[11]/RXD2/__SCL2/MAT3[1]_49") (pintype "passive"))
    )
    (net (code "87") (name "unconnected-(LPC_3-P0[16]{slash}RXD1{slash}__SSEL0{slash}SSEL-Pad63)") (class "Default")
      (node (ref "LPC_3") (pin "63") (pinfunction "P0[16]/RXD1/__SSEL0/SSEL_63") (pintype "passive"))
    )
    (net (code "88") (name "unconnected-(LPC_3-P0[21]{slash}RI1{slash}RD1-Pad57)") (class "Default")
      (node (ref "LPC_3") (pin "57") (pinfunction "P0[21]/RI1/RD1_57") (pintype "passive"))
    )
    (net (code "89") (name "unconnected-(LPC_3-P0[22]{slash}RTS1{slash}TD1-Pad56)") (class "Default")
      (node (ref "LPC_3") (pin "56") (pinfunction "P0[22]/RTS1/TD1_56") (pintype "passive"))
    )
    (net (code "90") (name "unconnected-(LPC_3-P0[23]{slash}AD0[0]{slash}__I2SRX_CLK{slash}__CAP3[0]-Pad9)") (class "Default")
      (node (ref "LPC_3") (pin "9") (pinfunction "P0[23]/AD0[0]/__I2SRX_CLK/__CAP3[0]_9") (pintype "passive"))
    )
    (net (code "91") (name "unconnected-(LPC_3-P0[24]{slash}AD0[1]{slash}__I2SRX_WS{slash}__CAP3[1]-Pad8)") (class "Default")
      (node (ref "LPC_3") (pin "8") (pinfunction "P0[24]/AD0[1]/__I2SRX_WS/__CAP3[1]_8") (pintype "passive"))
    )
    (net (code "92") (name "unconnected-(LPC_3-P0[25]{slash}AD0[2]{slash}__I2SRX_SDA{slash}__TXD3-Pad7)") (class "Default")
      (node (ref "LPC_3") (pin "7") (pinfunction "P0[25]/AD0[2]/__I2SRX_SDA/__TXD3_7") (pintype "passive"))
    )
    (net (code "93") (name "unconnected-(LPC_3-P0[26]{slash}AD0[3]{slash}__AOUT{slash}RXD3-Pad6)") (class "Default")
      (node (ref "LPC_3") (pin "6") (pinfunction "P0[26]/AD0[3]/__AOUT/RXD3_6") (pintype "passive"))
    )
    (net (code "94") (name "unconnected-(LPC_3-P0[27]{slash}SDA0{slash}__USB_SDA-Pad25)") (class "Default")
      (node (ref "LPC_3") (pin "25") (pinfunction "P0[27]/SDA0/__USB_SDA_25") (pintype "passive"))
    )
    (net (code "95") (name "unconnected-(LPC_3-P0[28]{slash}SCL0{slash}__USB_SCL-Pad24)") (class "Default")
      (node (ref "LPC_3") (pin "24") (pinfunction "P0[28]/SCL0/__USB_SCL_24") (pintype "passive"))
    )
    (net (code "96") (name "unconnected-(LPC_3-P0[29]{slash}USB_D+-Pad29)") (class "Default")
      (node (ref "LPC_3") (pin "29") (pinfunction "P0[29]/USB_D+_29") (pintype "passive"))
    )
    (net (code "97") (name "unconnected-(LPC_3-P0[30]{slash}USB_D--Pad30)") (class "Default")
      (node (ref "LPC_3") (pin "30") (pinfunction "P0[30]/USB_D-_30") (pintype "passive"))
    )
    (net (code "98") (name "unconnected-(LPC_3-P1[0]{slash}__ENET_TXD0-Pad95)") (class "Default")
      (node (ref "LPC_3") (pin "95") (pinfunction "P1[0]/__ENET_TXD0_95") (pintype "passive"))
    )
    (net (code "99") (name "unconnected-(LPC_3-P1[1]{slash}__ENET_TXD1-Pad94)") (class "Default")
      (node (ref "LPC_3") (pin "94") (pinfunction "P1[1]/__ENET_TXD1_94") (pintype "passive"))
    )
    (net (code "100") (name "unconnected-(LPC_3-P1[4]{slash}__ENET_TX_EN-Pad93)") (class "Default")
      (node (ref "LPC_3") (pin "93") (pinfunction "P1[4]/__ENET_TX_EN_93") (pintype "passive"))
    )
    (net (code "101") (name "unconnected-(LPC_3-P1[8]{slash}__ENET_CRS-Pad92)") (class "Default")
      (node (ref "LPC_3") (pin "92") (pinfunction "P1[8]/__ENET_CRS_92") (pintype "passive"))
    )
    (net (code "102") (name "unconnected-(LPC_3-P1[9]{slash}__ENET_RXD0-Pad91)") (class "Default")
      (node (ref "LPC_3") (pin "91") (pinfunction "P1[9]/__ENET_RXD0_91") (pintype "passive"))
    )
    (net (code "103") (name "unconnected-(LPC_3-P1[10]{slash}__ENET_RXD1-Pad90)") (class "Default")
      (node (ref "LPC_3") (pin "90") (pinfunction "P1[10]/__ENET_RXD1_90") (pintype "passive"))
    )
    (net (code "104") (name "unconnected-(LPC_3-P1[14]{slash}__ENET_RX_ER-Pad89)") (class "Default")
      (node (ref "LPC_3") (pin "89") (pinfunction "P1[14]/__ENET_RX_ER_89") (pintype "passive"))
    )
    (net (code "105") (name "unconnected-(LPC_3-P1[15]{slash}__ENET_REF_CLK-Pad88)") (class "Default")
      (node (ref "LPC_3") (pin "88") (pinfunction "P1[15]/__ENET_REF_CLK_88") (pintype "passive"))
    )
    (net (code "106") (name "unconnected-(LPC_3-P1[16]{slash}__ENET_MDC-Pad87)") (class "Default")
      (node (ref "LPC_3") (pin "87") (pinfunction "P1[16]/__ENET_MDC_87") (pintype "passive"))
    )
    (net (code "107") (name "unconnected-(LPC_3-P1[17]{slash}__ENET_MDIO-Pad86)") (class "Default")
      (node (ref "LPC_3") (pin "86") (pinfunction "P1[17]/__ENET_MDIO_86") (pintype "passive"))
    )
    (net (code "108") (name "unconnected-(LPC_3-P1[23]{slash}MCI1{slash}__PWM1[4]{slash}MISO0-Pad37)") (class "Default")
      (node (ref "LPC_3") (pin "37") (pinfunction "P1[23]/MCI1/__PWM1[4]/MISO0_37") (pintype "passive"))
    )
    (net (code "109") (name "unconnected-(LPC_3-P1[24]{slash}MCI2{slash}__PWM1[5]{slash}MOSI0-Pad38)") (class "Default")
      (node (ref "LPC_3") (pin "38") (pinfunction "P1[24]/MCI2/__PWM1[5]/MOSI0_38") (pintype "passive"))
    )
    (net (code "110") (name "unconnected-(LPC_3-P1[25]{slash}MCOA1{slash}__MAT1[1]-Pad39)") (class "Default")
      (node (ref "LPC_3") (pin "39") (pinfunction "P1[25]/MCOA1/__MAT1[1]_39") (pintype "passive"))
    )
    (net (code "111") (name "unconnected-(LPC_3-P1[26]{slash}MCOB1{slash}__PWM1[6]{slash}CAP0[0]-Pad40)") (class "Default")
      (node (ref "LPC_3") (pin "40") (pinfunction "P1[26]/MCOB1/__PWM1[6]/CAP0[0]_40") (pintype "passive"))
    )
    (net (code "112") (name "unconnected-(LPC_3-P1[28]{slash}MCOA2{slash}__PCAP1[0]{slash}__MAT0[0]-Pad44)") (class "Default")
      (node (ref "LPC_3") (pin "44") (pinfunction "P1[28]/MCOA2/__PCAP1[0]/__MAT0[0]_44") (pintype "passive"))
    )
    (net (code "113") (name "unconnected-(LPC_3-P1[29]{slash}MCOB2{slash}__PCAP1[1]{slash}__MAT0[1]-Pad45)") (class "Default")
      (node (ref "LPC_3") (pin "45") (pinfunction "P1[29]/MCOB2/__PCAP1[1]/__MAT0[1]_45") (pintype "passive"))
    )
    (net (code "114") (name "unconnected-(LPC_3-P1[30]{slash}VBUS{slash}__AD0[4]-Pad21)") (class "Default")
      (node (ref "LPC_3") (pin "21") (pinfunction "P1[30]/VBUS/__AD0[4]_21") (pintype "passive"))
    )
    (net (code "115") (name "unconnected-(LPC_3-P1[31]{slash}SCK1{slash}__AD0[5]-Pad20)") (class "Default")
      (node (ref "LPC_3") (pin "20") (pinfunction "P1[31]/SCK1/__AD0[5]_20") (pintype "passive"))
    )
    (net (code "116") (name "unconnected-(LPC_3-P3[25]{slash}MAT0[0]{slash}__PWM1[2]-Pad27)") (class "Default")
      (node (ref "LPC_3") (pin "27") (pinfunction "P3[25]/MAT0[0]/__PWM1[2]_27") (pintype "passive"))
    )
    (net (code "117") (name "unconnected-(LPC_3-P4[28]{slash}RX_MCLK{slash}__MAT2[0]{slash}TXD3-Pad82)") (class "Default")
      (node (ref "LPC_3") (pin "82") (pinfunction "P4[28]/RX_MCLK/__MAT2[0]/TXD3_82") (pintype "passive"))
    )
    (net (code "118") (name "unconnected-(LPC_3-P4[29]{slash}TX_MCLK__MAT2[1]{slash}RXD3-Pad85)") (class "Default")
      (node (ref "LPC_3") (pin "85") (pinfunction "P4[29]/TX_MCLK__MAT2[1]/RXD3_85") (pintype "passive"))
    )
    (net (code "119") (name "unconnected-(LPC_3-RSTOUT_L-Pad14)") (class "Default")
      (node (ref "LPC_3") (pin "14") (pinfunction "RSTOUT_L_14") (pintype "passive"))
    )
    (net (code "120") (name "unconnected-(LPC_3-RTCK-Pad100)") (class "Default")
      (node (ref "LPC_3") (pin "100") (pinfunction "RTCK_100") (pintype "passive"))
    )
    (net (code "121") (name "unconnected-(Program_SD3-NC-Pad7)") (class "Default")
      (node (ref "Program_SD3") (pin "7") (pinfunction "NC_7") (pintype "passive"))
    )
  )
)
